# FlightControl.net
KiCad netlist of a schematic drawn in Altium Designer
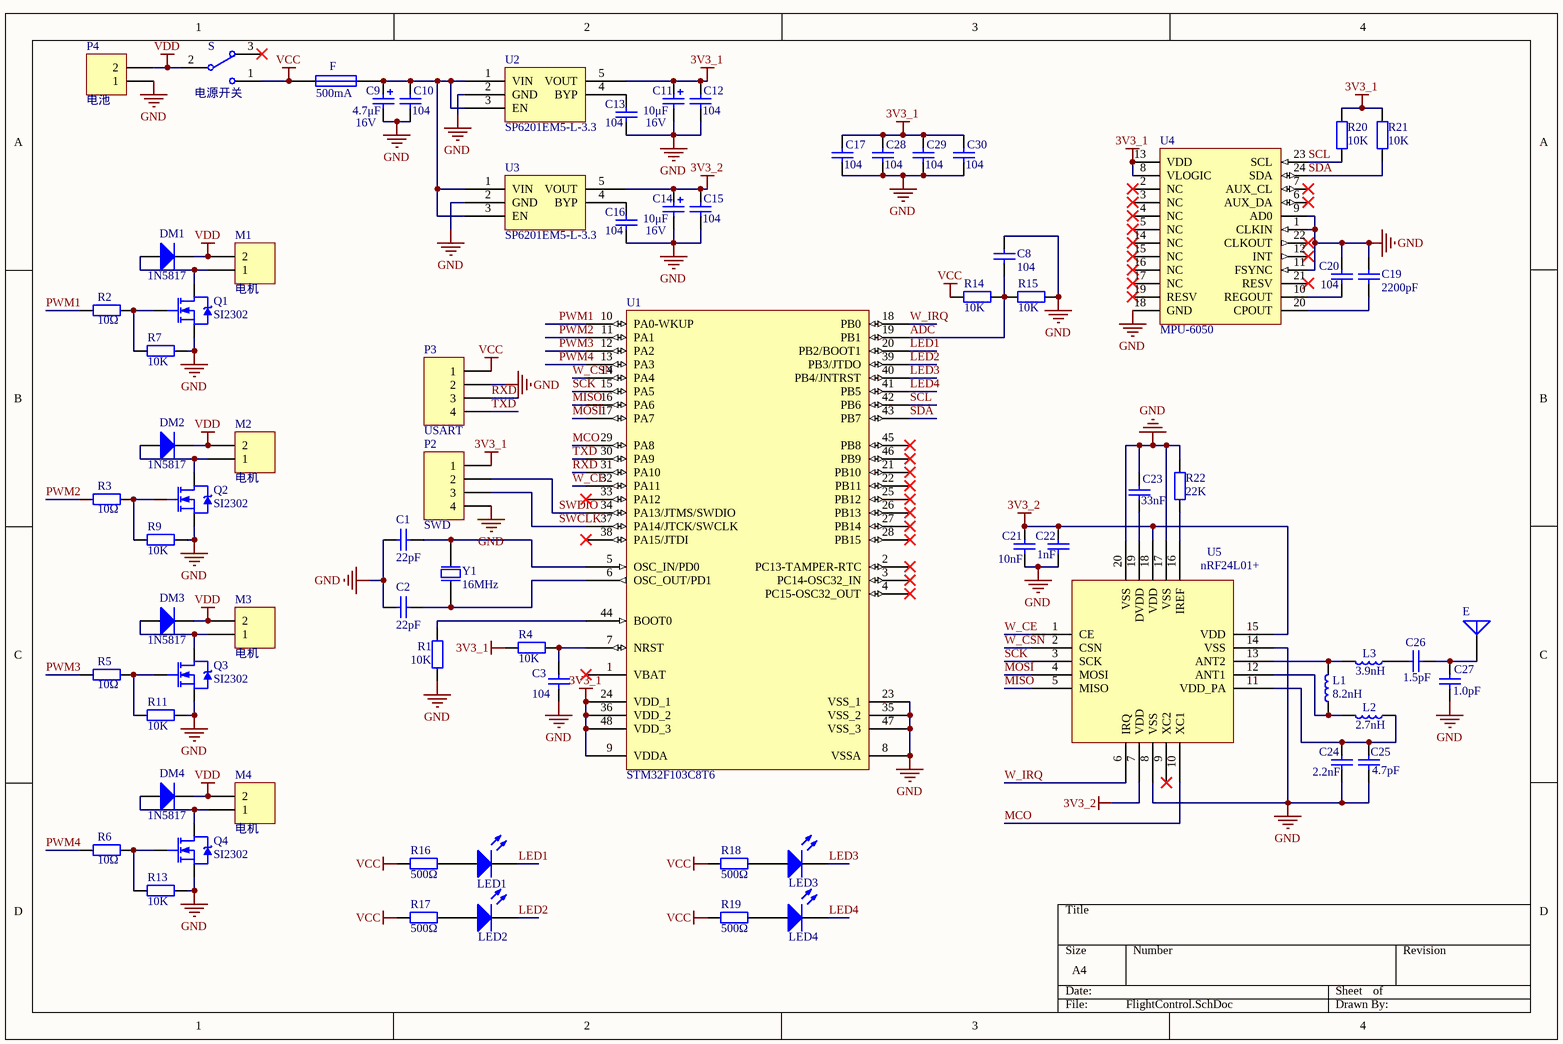
[diagram p0: FlightControl.SchDoc]

(export (version "E")
  (design (tool "Eeschema 10.0.6"))
  (components
    (comp (ref "C1")
      (value "22pF")
      (footprint "CC1608-0603")
      (description "Capacitor")
      (fields (field (name "PUBLISHER") "Altium Limited"))
      (libsource (lib "mini四轴") (part "Cap"))
    )
    (comp (ref "C2")
      (value "22pF")
      (footprint "CC1608-0603")
      (description "Capacitor")
      (fields (field (name "PUBLISHER") "Altium Limited"))
      (libsource (lib "mini四轴") (part "Cap"))
    )
    (comp (ref "C3")
      (value "104")
      (footprint "CC1608-0603")
      (description "Capacitor")
      (fields (field (name "PUBLISHER") "Altium Limited"))
      (libsource (lib "mini四轴") (part "Cap"))
    )
    (comp (ref "C8")
      (value "104")
      (footprint "CC1608-0603")
      (description "Capacitor")
      (fields (field (name "PUBLISHER") "Altium Limited"))
      (libsource (lib "mini四轴") (part "Cap"))
    )
    (comp (ref "C9")
      (value "4.7μF")
      (footprint "TAN-A-3216")
      (description "Polarized Capacitor (Radial)")
      (fields (field (name "VOLTAGE") "16V") (field (name "PUBLISHER") "Altium Limited"))
      (libsource (lib "我的集成库1") (part "Cap Tan"))
    )
    (comp (ref "C10")
      (value "104")
      (footprint "CC1608-0603")
      (description "Capacitor")
      (fields (field (name "PUBLISHER") "Altium Limited"))
      (libsource (lib "mini四轴") (part "Cap"))
    )
    (comp (ref "C11")
      (value "10μF")
      (footprint "TAN-A-3216")
      (description "Polarized Capacitor (Radial)")
      (fields (field (name "VOLTAGE") "16V") (field (name "PUBLISHER") "Altium Limited"))
      (libsource (lib "我的集成库1") (part "Cap Tan"))
    )
    (comp (ref "C12")
      (value "104")
      (footprint "CC1608-0603")
      (description "Capacitor")
      (fields (field (name "PUBLISHER") "Altium Limited"))
      (libsource (lib "mini四轴") (part "Cap"))
    )
    (comp (ref "C13")
      (value "104")
      (footprint "CC1608-0603")
      (description "Capacitor")
      (fields (field (name "PUBLISHER") "Altium Limited"))
      (libsource (lib "mini四轴") (part "Cap"))
    )
    (comp (ref "C14")
      (value "10μF")
      (footprint "TAN-A-3216")
      (description "Polarized Capacitor (Radial)")
      (fields (field (name "VOLTAGE") "16V") (field (name "PUBLISHER") "Altium Limited"))
      (libsource (lib "我的集成库1") (part "Cap Tan"))
    )
    (comp (ref "C15")
      (value "104")
      (footprint "CC1608-0603")
      (description "Capacitor")
      (fields (field (name "PUBLISHER") "Altium Limited"))
      (libsource (lib "mini四轴") (part "Cap"))
    )
    (comp (ref "C16")
      (value "104")
      (footprint "CC1608-0603")
      (description "Capacitor")
      (fields (field (name "PUBLISHER") "Altium Limited"))
      (libsource (lib "mini四轴") (part "Cap"))
    )
    (comp (ref "C17")
      (value "104")
      (footprint "CC1608-0603")
      (description "Capacitor")
      (fields (field (name "PUBLISHER") "Altium Limited"))
      (libsource (lib "mini四轴") (part "Cap"))
    )
    (comp (ref "C19")
      (value "2200pF")
      (footprint "CC1608-0603")
      (description "Capacitor")
      (fields (field (name "PUBLISHER") "Altium Limited"))
      (libsource (lib "mini四轴") (part "Cap"))
    )
    (comp (ref "C20")
      (value "104")
      (footprint "CC1608-0603")
      (description "Capacitor")
      (fields (field (name "PUBLISHER") "Altium Limited"))
      (libsource (lib "mini四轴") (part "Cap"))
    )
    (comp (ref "C21")
      (value "10nF")
      (footprint "CC1608-0603")
      (description "Capacitor")
      (fields (field (name "PUBLISHER") "Altium Limited"))
      (libsource (lib "mini四轴") (part "Cap"))
    )
    (comp (ref "C22")
      (value "1nF")
      (footprint "CC1608-0603")
      (description "Capacitor")
      (fields (field (name "PUBLISHER") "Altium Limited"))
      (libsource (lib "mini四轴") (part "Cap"))
    )
    (comp (ref "C23")
      (value "33nF")
      (footprint "CC1608-0603")
      (description "Capacitor")
      (fields (field (name "PUBLISHER") "Altium Limited"))
      (libsource (lib "mini四轴") (part "Cap"))
    )
    (comp (ref "C24")
      (value "2.2nF")
      (footprint "CC1608-0603")
      (description "Capacitor")
      (fields (field (name "PUBLISHER") "Altium Limited"))
      (libsource (lib "mini四轴") (part "Cap"))
    )
    (comp (ref "C25")
      (value "4.7pF")
      (footprint "CC1608-0603")
      (description "Capacitor")
      (fields (field (name "PUBLISHER") "Altium Limited"))
      (libsource (lib "mini四轴") (part "Cap"))
    )
    (comp (ref "C26")
      (value "1.5pF")
      (footprint "CC1608-0603")
      (description "Capacitor")
      (fields (field (name "PUBLISHER") "Altium Limited"))
      (libsource (lib "mini四轴") (part "Cap"))
    )
    (comp (ref "C27")
      (value "1.0pF")
      (footprint "CC1608-0603")
      (description "Capacitor")
      (fields (field (name "PUBLISHER") "Altium Limited"))
      (libsource (lib "mini四轴") (part "Cap"))
    )
    (comp (ref "C28")
      (value "104")
      (footprint "CC1608-0603")
      (description "Capacitor")
      (fields (field (name "PUBLISHER") "Altium Limited"))
      (libsource (lib "mini四轴") (part "Cap"))
    )
    (comp (ref "C29")
      (value "104")
      (footprint "CC1608-0603")
      (description "Capacitor")
      (fields (field (name "PUBLISHER") "Altium Limited"))
      (libsource (lib "mini四轴") (part "Cap"))
    )
    (comp (ref "C30")
      (value "104")
      (footprint "CC1608-0603")
      (description "Capacitor")
      (fields (field (name "PUBLISHER") "Altium Limited"))
      (libsource (lib "mini四轴") (part "Cap"))
    )
    (comp (ref "DM1")
      (value "1N5817")
      (footprint "SOD-123 (1206)")
      (libsource (lib "我的集成库1") (part "二极管  SOD-323"))
    )
    (comp (ref "DM2")
      (value "1N5817")
      (footprint "SOD-123 (1206)")
      (libsource (lib "我的集成库1") (part "二极管  SOD-323"))
    )
    (comp (ref "DM3")
      (value "1N5817")
      (footprint "SOD-123 (1206)")
      (libsource (lib "我的集成库1") (part "二极管  SOD-323"))
    )
    (comp (ref "DM4")
      (value "1N5817")
      (footprint "SOD-123 (1206)")
      (libsource (lib "我的集成库1") (part "二极管  SOD-323"))
    )
    (comp (ref "E")
      (value "~")
      (footprint "Chip Antenna")
      (description "Generic Antenna")
      (fields (field (name "PUBLISHER") "Altium Limited"))
      (libsource (lib "mini四轴") (part "Antenna"))
    )
    (comp (ref "F")
      (value "500mA")
      (footprint "CR2012-0805")
      (description "Fuse")
      (fields (field (name "PUBLISHER") "Altium Limited"))
      (libsource (lib "我的集成库1") (part "Fuse"))
    )
    (comp (ref "L1")
      (value "8.2nH")
      (footprint "CC1608[0603]")
      (description "Inductor")
      (fields (field (name "PUBLISHER") "Altium Limited"))
      (libsource (lib "mini四轴") (part "Inductor"))
    )
    (comp (ref "L2")
      (value "2.7nH")
      (footprint "CC1608[0603]")
      (description "Inductor")
      (fields (field (name "PUBLISHER") "Altium Limited"))
      (libsource (lib "mini四轴") (part "Inductor"))
    )
    (comp (ref "L3")
      (value "3.9nH")
      (footprint "CC1608[0603]")
      (description "Inductor")
      (fields (field (name "PUBLISHER") "Altium Limited"))
      (libsource (lib "mini四轴") (part "Inductor"))
    )
    (comp (ref "LED1")
      (value "LED Chip")
      (footprint "CLED2012-0805")
      (description "Typical Chip LED")
      (fields (field (name "PUBLISHER") "Altium Limited"))
      (libsource (lib "我的集成库1") (part "LED Chip"))
    )
    (comp (ref "LED2")
      (value "LED Chip")
      (footprint "CLED2012-0805")
      (description "Typical Chip LED")
      (fields (field (name "PUBLISHER") "Altium Limited"))
      (libsource (lib "我的集成库1") (part "LED Chip"))
    )
    (comp (ref "LED3")
      (value "LED Chip")
      (footprint "CLED2012-0805")
      (description "Typical Chip LED")
      (fields (field (name "PUBLISHER") "Altium Limited"))
      (libsource (lib "我的集成库1") (part "LED Chip"))
    )
    (comp (ref "LED4")
      (value "LED Chip")
      (footprint "CLED2012-0805")
      (description "Typical Chip LED")
      (fields (field (name "PUBLISHER") "Altium Limited"))
      (libsource (lib "我的集成库1") (part "LED Chip"))
    )
    (comp (ref "M1")
      (value "电机")
      (footprint "HDR1X2")
      (description "Header, 2-Pin")
      (fields (field (name "PUBLISHER") "Altium Limited"))
      (libsource (lib "我的集成库1") (part "Header 2"))
    )
    (comp (ref "M2")
      (value "电机")
      (footprint "HDR1X2")
      (description "Header, 2-Pin")
      (fields (field (name "PUBLISHER") "Altium Limited"))
      (libsource (lib "我的集成库1") (part "Header 2"))
    )
    (comp (ref "M3")
      (value "电机")
      (footprint "HDR1X2")
      (description "Header, 2-Pin")
      (fields (field (name "PUBLISHER") "Altium Limited"))
      (libsource (lib "我的集成库1") (part "Header 2"))
    )
    (comp (ref "M4")
      (value "电机")
      (footprint "HDR1X2")
      (description "Header, 2-Pin")
      (fields (field (name "PUBLISHER") "Altium Limited"))
      (libsource (lib "我的集成库1") (part "Header 2"))
    )
    (comp (ref "P2")
      (value "SWD")
      (footprint "HDR1X4")
      (description "Header, 4-Pin")
      (fields (field (name "PUBLISHER") "Altium Limited"))
      (libsource (lib "我的集成库1") (part "Header 4"))
    )
    (comp (ref "P3")
      (value "USART")
      (footprint "HDR1X4")
      (description "Header, 4-Pin")
      (fields (field (name "PUBLISHER") "Altium Limited"))
      (libsource (lib "我的集成库1") (part "Header 4"))
    )
    (comp (ref "P4")
      (value "电池")
      (footprint "HDR1X2")
      (description "Header, 2-Pin")
      (fields (field (name "PUBLISHER") "Altium Limited"))
      (libsource (lib "") (part "Header 2_1"))
    )
    (comp (ref "Q1")
      (value "SI2302")
      (footprint "SOT23")
      (description "N-Channel Power MOSFET")
      (fields (field (name "PUBLISHER") "Altium Limited"))
      (libsource (lib "mini四轴") (part "NMOS"))
    )
    (comp (ref "Q2")
      (value "SI2302")
      (footprint "SOT23")
      (description "N-Channel Power MOSFET")
      (fields (field (name "PUBLISHER") "Altium Limited"))
      (libsource (lib "mini四轴") (part "NMOS"))
    )
    (comp (ref "Q3")
      (value "SI2302")
      (footprint "SOT23")
      (description "N-Channel Power MOSFET")
      (fields (field (name "PUBLISHER") "Altium Limited"))
      (libsource (lib "mini四轴") (part "NMOS"))
    )
    (comp (ref "Q4")
      (value "SI2302")
      (footprint "SOT23")
      (description "N-Channel Power MOSFET")
      (fields (field (name "PUBLISHER") "Altium Limited"))
      (libsource (lib "mini四轴") (part "NMOS"))
    )
    (comp (ref "R1")
      (value "10K")
      (footprint "CR1608-0603")
      (description "Resistor")
      (fields (field (name "PUBLISHER") "Altium Limited"))
      (libsource (lib "") (part "Resistor Chip_1"))
    )
    (comp (ref "R2")
      (value "10Ω")
      (footprint "CR1608-0603")
      (description "Resistor")
      (fields (field (name "PUBLISHER") "Altium Limited"))
      (libsource (lib "我的集成库1") (part "Resistor Chip"))
    )
    (comp (ref "R3")
      (value "10Ω")
      (footprint "CR1608-0603")
      (description "Resistor")
      (fields (field (name "PUBLISHER") "Altium Limited"))
      (libsource (lib "我的集成库1") (part "Resistor Chip"))
    )
    (comp (ref "R4")
      (value "10K")
      (footprint "CR1608-0603")
      (description "Resistor")
      (fields (field (name "PUBLISHER") "Altium Limited"))
      (libsource (lib "我的集成库1") (part "Resistor Chip"))
    )
    (comp (ref "R5")
      (value "10Ω")
      (footprint "CR1608-0603")
      (description "Resistor")
      (fields (field (name "PUBLISHER") "Altium Limited"))
      (libsource (lib "我的集成库1") (part "Resistor Chip"))
    )
    (comp (ref "R6")
      (value "10Ω")
      (footprint "CR1608-0603")
      (description "Resistor")
      (fields (field (name "PUBLISHER") "Altium Limited"))
      (libsource (lib "我的集成库1") (part "Resistor Chip"))
    )
    (comp (ref "R7")
      (value "10K")
      (footprint "CR1608-0603")
      (description "Resistor")
      (fields (field (name "PUBLISHER") "Altium Limited"))
      (libsource (lib "我的集成库1") (part "Resistor Chip"))
    )
    (comp (ref "R9")
      (value "10K")
      (footprint "CR1608-0603")
      (description "Resistor")
      (fields (field (name "PUBLISHER") "Altium Limited"))
      (libsource (lib "我的集成库1") (part "Resistor Chip"))
    )
    (comp (ref "R11")
      (value "10K")
      (footprint "CR1608-0603")
      (description "Resistor")
      (fields (field (name "PUBLISHER") "Altium Limited"))
      (libsource (lib "我的集成库1") (part "Resistor Chip"))
    )
    (comp (ref "R13")
      (value "10K")
      (footprint "CR1608-0603")
      (description "Resistor")
      (fields (field (name "PUBLISHER") "Altium Limited"))
      (libsource (lib "我的集成库1") (part "Resistor Chip"))
    )
    (comp (ref "R14")
      (value "10K")
      (footprint "CR1608-0603")
      (description "Resistor")
      (fields (field (name "PUBLISHER") "Altium Limited"))
      (libsource (lib "我的集成库1") (part "Resistor Chip"))
    )
    (comp (ref "R15")
      (value "10K")
      (footprint "CR1608-0603")
      (description "Resistor")
      (fields (field (name "PUBLISHER") "Altium Limited"))
      (libsource (lib "我的集成库1") (part "Resistor Chip"))
    )
    (comp (ref "R16")
      (value "500Ω")
      (footprint "CR1608-0603")
      (description "Resistor")
      (fields (field (name "PUBLISHER") "Altium Limited"))
      (libsource (lib "我的集成库1") (part "Resistor Chip"))
    )
    (comp (ref "R17")
      (value "500Ω")
      (footprint "CR1608-0603")
      (description "Resistor")
      (fields (field (name "PUBLISHER") "Altium Limited"))
      (libsource (lib "我的集成库1") (part "Resistor Chip"))
    )
    (comp (ref "R18")
      (value "500Ω")
      (footprint "CR1608-0603")
      (description "Resistor")
      (fields (field (name "PUBLISHER") "Altium Limited"))
      (libsource (lib "我的集成库1") (part "Resistor Chip"))
    )
    (comp (ref "R19")
      (value "500Ω")
      (footprint "CR1608-0603")
      (description "Resistor")
      (fields (field (name "PUBLISHER") "Altium Limited"))
      (libsource (lib "我的集成库1") (part "Resistor Chip"))
    )
    (comp (ref "R20")
      (value "10K")
      (footprint "CR1608-0603")
      (description "Resistor")
      (fields (field (name "PUBLISHER") "Altium Limited"))
      (libsource (lib "") (part "Resistor Chip_1"))
    )
    (comp (ref "R21")
      (value "10K")
      (footprint "CR1608-0603")
      (description "Resistor")
      (fields (field (name "PUBLISHER") "Altium Limited"))
      (libsource (lib "") (part "Resistor Chip_1"))
    )
    (comp (ref "R22")
      (value "22K")
      (footprint "CR1608-0603")
      (description "Resistor")
      (fields (field (name "PUBLISHER") "Altium Limited"))
      (libsource (lib "") (part "Resistor Chip_1"))
    )
    (comp (ref "S")
      (value "电源开关")
      (footprint "MSK-12C02-1")
      (description "SPDT Subminiature Toggle Switch, Right Angle Mounting, Vertical Actuation")
      (fields (field (name "PUBLISHER") "Altium Limited"))
      (libsource (lib "mini四轴") (part "SW-SPDT"))
    )
    (comp (ref "U1")
      (value "STM32F103C8T6")
      (footprint "LQFP48_N")
      (description "STM32 ARM-based 32-bit MCU with 64 Kbytes Flash, 48-pin LQFP, Industrial Temperature")
      (fields (field (name "PUBLISHER") "*"))
      (libsource (lib "STM32") (part "STM32F103C8T6"))
    )
    (comp (ref "U2")
      (value "SP6201EM5-L-3.3")
      (footprint "SO-G5/NS")
      (libsource (lib "mini四轴") (part "PAM3101"))
    )
    (comp (ref "U3")
      (value "SP6201EM5-L-3.3")
      (footprint "SO-G5/NS")
      (libsource (lib "mini四轴") (part "PAM3101"))
    )
    (comp (ref "U4")
      (value "MPU-6050")
      (footprint "QFN50P400X400X95-24N")
      (description "3-axis gyroscope and 3-axis accelerometer")
      (libsource (lib "mini四轴") (part "MPU-6050"))
    )
    (comp (ref "U5")
      (value "nRF24L01+")
      (footprint "QFN50P400X400-20V5N")
      (libsource (lib "mini四轴") (part "nRF24L01+"))
    )
    (comp (ref "Y1")
      (value "8MHz")
      (footprint "XTAL-PINGBI")
      (description "Crystal Oscillator")
      (fields (field (name "FREQUENCY") "16MHz") (field (name "PUBLISHER") "Altium Limited"))
      (libsource (lib "我的集成库1") (part "XTAL"))
    )
  )
  (nets
    (net (code "1") (name "/ADC") (class "Default")
      (node (ref "C8") (pin "2") (pinfunction "2_2") (pintype "passive"))
      (node (ref "R14") (pin "2") (pinfunction "2_2") (pintype "passive"))
      (node (ref "R15") (pin "1") (pinfunction "1_1") (pintype "passive"))
      (node (ref "U1") (pin "19") (pinfunction "PB1_19") (pintype "bidirectional"))
    )
    (net (code "2") (name "/LED1") (class "Default")
      (node (ref "LED1") (pin "2") (pinfunction "K_2") (pintype "passive"))
      (node (ref "U1") (pin "20") (pinfunction "PB2/BOOT1_20") (pintype "bidirectional"))
    )
    (net (code "3") (name "/LED2") (class "Default")
      (node (ref "LED2") (pin "2") (pinfunction "K_2") (pintype "passive"))
      (node (ref "U1") (pin "39") (pinfunction "PB3/JTDO_39") (pintype "bidirectional"))
    )
    (net (code "4") (name "/LED3") (class "Default")
      (node (ref "LED3") (pin "2") (pinfunction "K_2") (pintype "passive"))
      (node (ref "U1") (pin "40") (pinfunction "PB4/JNTRST_40") (pintype "bidirectional"))
    )
    (net (code "5") (name "/LED4") (class "Default")
      (node (ref "LED4") (pin "2") (pinfunction "K_2") (pintype "passive"))
      (node (ref "U1") (pin "41") (pinfunction "PB5_41") (pintype "bidirectional"))
    )
    (net (code "6") (name "/MCO") (class "Default")
      (node (ref "U1") (pin "29") (pinfunction "PA8_29") (pintype "bidirectional"))
      (node (ref "U5") (pin "10") (pinfunction "XC1_10") (pintype "passive"))
    )
    (net (code "7") (name "/MISO") (class "Default")
      (node (ref "U1") (pin "16") (pinfunction "PA6_16") (pintype "bidirectional"))
      (node (ref "U5") (pin "5") (pinfunction "MISO_5") (pintype "passive"))
    )
    (net (code "8") (name "/MOSI") (class "Default")
      (node (ref "U1") (pin "17") (pinfunction "PA7_17") (pintype "bidirectional"))
      (node (ref "U5") (pin "4") (pinfunction "MOSI_4") (pintype "passive"))
    )
    (net (code "9") (name "/PWM1") (class "Default")
      (node (ref "R2") (pin "1") (pinfunction "1_1") (pintype "passive"))
      (node (ref "U1") (pin "10") (pinfunction "PA0-WKUP_10") (pintype "bidirectional"))
    )
    (net (code "10") (name "/PWM2") (class "Default")
      (node (ref "R3") (pin "1") (pinfunction "1_1") (pintype "passive"))
      (node (ref "U1") (pin "11") (pinfunction "PA1_11") (pintype "bidirectional"))
    )
    (net (code "11") (name "/PWM3") (class "Default")
      (node (ref "R5") (pin "1") (pinfunction "1_1") (pintype "passive"))
      (node (ref "U1") (pin "12") (pinfunction "PA2_12") (pintype "bidirectional"))
    )
    (net (code "12") (name "/PWM4") (class "Default")
      (node (ref "R6") (pin "1") (pinfunction "1_1") (pintype "passive"))
      (node (ref "U1") (pin "13") (pinfunction "PA3_13") (pintype "bidirectional"))
    )
    (net (code "13") (name "/RXD") (class "Default")
      (node (ref "P3") (pin "3") (pinfunction "3_3") (pintype "passive"))
      (node (ref "U1") (pin "31") (pinfunction "PA10_31") (pintype "bidirectional"))
    )
    (net (code "14") (name "/SCK") (class "Default")
      (node (ref "U1") (pin "15") (pinfunction "PA5_15") (pintype "bidirectional"))
      (node (ref "U5") (pin "3") (pinfunction "SCK_3") (pintype "passive"))
    )
    (net (code "15") (name "/SCL") (class "Default")
      (node (ref "R20") (pin "1") (pinfunction "1_1") (pintype "passive"))
      (node (ref "U1") (pin "42") (pinfunction "PB6_42") (pintype "bidirectional"))
      (node (ref "U4") (pin "23") (pinfunction "SCL_23") (pintype "input"))
    )
    (net (code "16") (name "/SDA") (class "Default")
      (node (ref "R21") (pin "1") (pinfunction "1_1") (pintype "passive"))
      (node (ref "U1") (pin "43") (pinfunction "PB7_43") (pintype "bidirectional"))
      (node (ref "U4") (pin "24") (pinfunction "SDA_24") (pintype "bidirectional"))
    )
    (net (code "17") (name "/SWCLK") (class "Default")
      (node (ref "P2") (pin "3") (pinfunction "3_3") (pintype "passive"))
      (node (ref "U1") (pin "37") (pinfunction "PA14/JTCK/SWCLK_37") (pintype "bidirectional"))
    )
    (net (code "18") (name "/SWDIO") (class "Default")
      (node (ref "P2") (pin "2") (pinfunction "2_2") (pintype "passive"))
      (node (ref "U1") (pin "34") (pinfunction "PA13/JTMS/SWDIO_34") (pintype "bidirectional"))
    )
    (net (code "19") (name "/TXD") (class "Default")
      (node (ref "P3") (pin "4") (pinfunction "4_4") (pintype "passive"))
      (node (ref "U1") (pin "30") (pinfunction "PA9_30") (pintype "bidirectional"))
    )
    (net (code "20") (name "/W_CE") (class "Default")
      (node (ref "U1") (pin "32") (pinfunction "PA11_32") (pintype "bidirectional"))
      (node (ref "U5") (pin "1") (pinfunction "CE_1") (pintype "passive"))
    )
    (net (code "21") (name "/W_CSN") (class "Default")
      (node (ref "U1") (pin "14") (pinfunction "PA4_14") (pintype "bidirectional"))
      (node (ref "U5") (pin "2") (pinfunction "CSN_2") (pintype "passive"))
    )
    (net (code "22") (name "/W_IRQ") (class "Default")
      (node (ref "U1") (pin "18") (pinfunction "PB0_18") (pintype "bidirectional"))
      (node (ref "U5") (pin "6") (pinfunction "IRQ_6") (pintype "passive"))
    )
    (net (code "23") (name "3V3_1") (class "Default")
      (node (ref "C11") (pin "2") (pinfunction "1_2") (pintype "passive"))
      (node (ref "C12") (pin "2") (pinfunction "2_2") (pintype "passive"))
      (node (ref "C17") (pin "2") (pinfunction "2_2") (pintype "passive"))
      (node (ref "C28") (pin "2") (pinfunction "2_2") (pintype "passive"))
      (node (ref "C29") (pin "2") (pinfunction "2_2") (pintype "passive"))
      (node (ref "C30") (pin "2") (pinfunction "2_2") (pintype "passive"))
      (node (ref "P2") (pin "1") (pinfunction "1_1") (pintype "passive"))
      (node (ref "R20") (pin "2") (pinfunction "2_2") (pintype "passive"))
      (node (ref "R21") (pin "2") (pinfunction "2_2") (pintype "passive"))
      (node (ref "R4") (pin "1") (pinfunction "1_1") (pintype "passive"))
      (node (ref "U1") (pin "24") (pinfunction "VDD_1_24") (pintype "power_in"))
      (node (ref "U1") (pin "36") (pinfunction "VDD_2_36") (pintype "power_in"))
      (node (ref "U1") (pin "48") (pinfunction "VDD_3_48") (pintype "power_in"))
      (node (ref "U1") (pin "9") (pinfunction "VDDA_9") (pintype "power_in"))
      (node (ref "U2") (pin "5") (pinfunction "VOUT_5") (pintype "passive"))
      (node (ref "U4") (pin "13") (pinfunction "VDD_13") (pintype "power_in"))
      (node (ref "U4") (pin "8") (pinfunction "VLOGIC_8") (pintype "power_in"))
    )
    (net (code "24") (name "3V3_2") (class "Default")
      (node (ref "C14") (pin "2") (pinfunction "1_2") (pintype "passive"))
      (node (ref "C15") (pin "2") (pinfunction "2_2") (pintype "passive"))
      (node (ref "C21") (pin "1") (pinfunction "1_1") (pintype "passive"))
      (node (ref "C22") (pin "1") (pinfunction "1_1") (pintype "passive"))
      (node (ref "U3") (pin "5") (pinfunction "VOUT_5") (pintype "passive"))
      (node (ref "U5") (pin "15") (pinfunction "VDD_15") (pintype "passive"))
      (node (ref "U5") (pin "18") (pinfunction "VDD_18") (pintype "passive"))
      (node (ref "U5") (pin "7") (pinfunction "VDD_7") (pintype "passive"))
    )
    (net (code "25") (name "GND") (class "Default")
      (node (ref "C1") (pin "1") (pinfunction "1_1") (pintype "passive"))
      (node (ref "C10") (pin "1") (pinfunction "1_1") (pintype "passive"))
      (node (ref "C11") (pin "1") (pinfunction "2_1") (pintype "passive"))
      (node (ref "C12") (pin "1") (pinfunction "1_1") (pintype "passive"))
      (node (ref "C13") (pin "1") (pinfunction "1_1") (pintype "passive"))
      (node (ref "C14") (pin "1") (pinfunction "2_1") (pintype "passive"))
      (node (ref "C15") (pin "1") (pinfunction "1_1") (pintype "passive"))
      (node (ref "C16") (pin "1") (pinfunction "1_1") (pintype "passive"))
      (node (ref "C17") (pin "1") (pinfunction "1_1") (pintype "passive"))
      (node (ref "C19") (pin "1") (pinfunction "1_1") (pintype "passive"))
      (node (ref "C2") (pin "1") (pinfunction "1_1") (pintype "passive"))
      (node (ref "C20") (pin "1") (pinfunction "1_1") (pintype "passive"))
      (node (ref "C21") (pin "2") (pinfunction "2_2") (pintype "passive"))
      (node (ref "C22") (pin "2") (pinfunction "2_2") (pintype "passive"))
      (node (ref "C23") (pin "1") (pinfunction "1_1") (pintype "passive"))
      (node (ref "C24") (pin "2") (pinfunction "2_2") (pintype "passive"))
      (node (ref "C25") (pin "2") (pinfunction "2_2") (pintype "passive"))
      (node (ref "C27") (pin "1") (pinfunction "1_1") (pintype "passive"))
      (node (ref "C28") (pin "1") (pinfunction "1_1") (pintype "passive"))
      (node (ref "C29") (pin "1") (pinfunction "1_1") (pintype "passive"))
      (node (ref "C3") (pin "1") (pinfunction "1_1") (pintype "passive"))
      (node (ref "C30") (pin "1") (pinfunction "1_1") (pintype "passive"))
      (node (ref "C8") (pin "1") (pinfunction "1_1") (pintype "passive"))
      (node (ref "C9") (pin "1") (pinfunction "2_1") (pintype "passive"))
      (node (ref "P2") (pin "4") (pinfunction "4_4") (pintype "passive"))
      (node (ref "P3") (pin "2") (pinfunction "2_2") (pintype "passive"))
      (node (ref "P4") (pin "1") (pinfunction "1_1") (pintype "passive"))
      (node (ref "Q1") (pin "3") (pinfunction "S_3") (pintype "passive"))
      (node (ref "Q2") (pin "3") (pinfunction "S_3") (pintype "passive"))
      (node (ref "Q3") (pin "3") (pinfunction "S_3") (pintype "passive"))
      (node (ref "Q4") (pin "3") (pinfunction "S_3") (pintype "passive"))
      (node (ref "R1") (pin "1") (pinfunction "1_1") (pintype "passive"))
      (node (ref "R11") (pin "2") (pinfunction "2_2") (pintype "passive"))
      (node (ref "R13") (pin "2") (pinfunction "2_2") (pintype "passive"))
      (node (ref "R15") (pin "2") (pinfunction "2_2") (pintype "passive"))
      (node (ref "R22") (pin "2") (pinfunction "2_2") (pintype "passive"))
      (node (ref "R7") (pin "2") (pinfunction "2_2") (pintype "passive"))
      (node (ref "R9") (pin "2") (pinfunction "2_2") (pintype "passive"))
      (node (ref "U1") (pin "23") (pinfunction "VSS_1_23") (pintype "power_in"))
      (node (ref "U1") (pin "35") (pinfunction "VSS_2_35") (pintype "power_in"))
      (node (ref "U1") (pin "47") (pinfunction "VSS_3_47") (pintype "power_in"))
      (node (ref "U1") (pin "8") (pinfunction "VSSA_8") (pintype "power_in"))
      (node (ref "U2") (pin "2") (pinfunction "GND_2") (pintype "passive"))
      (node (ref "U3") (pin "2") (pinfunction "GND_2") (pintype "passive"))
      (node (ref "U4") (pin "1") (pinfunction "CLKIN_1") (pintype "input"))
      (node (ref "U4") (pin "11") (pinfunction "FSYNC_11") (pintype "input"))
      (node (ref "U4") (pin "18") (pinfunction "GND_18") (pintype "power_in"))
      (node (ref "U4") (pin "9") (pinfunction "AD0_9") (pintype "power_in"))
      (node (ref "U5") (pin "14") (pinfunction "VSS_14") (pintype "passive"))
      (node (ref "U5") (pin "17") (pinfunction "VSS_17") (pintype "passive"))
      (node (ref "U5") (pin "20") (pinfunction "VSS_20") (pintype "passive"))
      (node (ref "U5") (pin "8") (pinfunction "VSS_8") (pintype "passive"))
    )
    (net (code "26") (name "Net-(C9-1)") (class "Default")
      (node (ref "C10") (pin "2") (pinfunction "2_2") (pintype "passive"))
      (node (ref "C9") (pin "2") (pinfunction "1_2") (pintype "passive"))
      (node (ref "F") (pin "2") (pinfunction "2_2") (pintype "passive"))
      (node (ref "U2") (pin "1") (pinfunction "VIN_1") (pintype "passive"))
      (node (ref "U2") (pin "3") (pinfunction "EN_3") (pintype "passive"))
      (node (ref "U3") (pin "1") (pinfunction "VIN_1") (pintype "passive"))
      (node (ref "U3") (pin "3") (pinfunction "EN_3") (pintype "passive"))
    )
    (net (code "27") (name "Net-(C26-Pad1)") (class "Default")
      (node (ref "C26") (pin "1") (pinfunction "1_1") (pintype "passive"))
      (node (ref "L3") (pin "1") (pinfunction "1_1") (pintype "passive"))
    )
    (net (code "28") (name "Net-(DM1-A)") (class "Default")
      (node (ref "DM1") (pin "1") (pinfunction "A_1") (pintype "passive"))
      (node (ref "M1") (pin "1") (pinfunction "1_1") (pintype "passive"))
      (node (ref "Q1") (pin "2") (pinfunction "D_2") (pintype "passive"))
    )
    (net (code "29") (name "Net-(DM2-A)") (class "Default")
      (node (ref "DM2") (pin "1") (pinfunction "A_1") (pintype "passive"))
      (node (ref "M2") (pin "1") (pinfunction "1_1") (pintype "passive"))
      (node (ref "Q2") (pin "2") (pinfunction "D_2") (pintype "passive"))
    )
    (net (code "30") (name "Net-(DM3-A)") (class "Default")
      (node (ref "DM3") (pin "1") (pinfunction "A_1") (pintype "passive"))
      (node (ref "M3") (pin "1") (pinfunction "1_1") (pintype "passive"))
      (node (ref "Q3") (pin "2") (pinfunction "D_2") (pintype "passive"))
    )
    (net (code "31") (name "Net-(DM4-A)") (class "Default")
      (node (ref "DM4") (pin "1") (pinfunction "A_1") (pintype "passive"))
      (node (ref "M4") (pin "1") (pinfunction "1_1") (pintype "passive"))
      (node (ref "Q4") (pin "2") (pinfunction "D_2") (pintype "passive"))
    )
    (net (code "32") (name "Net-(E-A)") (class "Default")
      (node (ref "C26") (pin "2") (pinfunction "2_2") (pintype "passive"))
      (node (ref "C27") (pin "2") (pinfunction "2_2") (pintype "passive"))
      (node (ref "E") (pin "1") (pinfunction "A_1") (pintype "passive"))
    )
    (net (code "33") (name "Net-(LED1-A)") (class "Default")
      (node (ref "LED1") (pin "1") (pinfunction "A_1") (pintype "passive"))
      (node (ref "R16") (pin "2") (pinfunction "2_2") (pintype "passive"))
    )
    (net (code "34") (name "Net-(LED2-A)") (class "Default")
      (node (ref "LED2") (pin "1") (pinfunction "A_1") (pintype "passive"))
      (node (ref "R17") (pin "2") (pinfunction "2_2") (pintype "passive"))
    )
    (net (code "35") (name "Net-(LED3-A)") (class "Default")
      (node (ref "LED3") (pin "1") (pinfunction "A_1") (pintype "passive"))
      (node (ref "R18") (pin "2") (pinfunction "2_2") (pintype "passive"))
    )
    (net (code "36") (name "Net-(LED4-A)") (class "Default")
      (node (ref "LED4") (pin "1") (pinfunction "A_1") (pintype "passive"))
      (node (ref "R19") (pin "2") (pinfunction "2_2") (pintype "passive"))
    )
    (net (code "37") (name "Net-(Q1-G)") (class "Default")
      (node (ref "Q1") (pin "1") (pinfunction "G_1") (pintype "passive"))
      (node (ref "R2") (pin "2") (pinfunction "2_2") (pintype "passive"))
      (node (ref "R7") (pin "1") (pinfunction "1_1") (pintype "passive"))
    )
    (net (code "38") (name "Net-(Q2-G)") (class "Default")
      (node (ref "Q2") (pin "1") (pinfunction "G_1") (pintype "passive"))
      (node (ref "R3") (pin "2") (pinfunction "2_2") (pintype "passive"))
      (node (ref "R9") (pin "1") (pinfunction "1_1") (pintype "passive"))
    )
    (net (code "39") (name "Net-(Q3-G)") (class "Default")
      (node (ref "Q3") (pin "1") (pinfunction "G_1") (pintype "passive"))
      (node (ref "R11") (pin "1") (pinfunction "1_1") (pintype "passive"))
      (node (ref "R5") (pin "2") (pinfunction "2_2") (pintype "passive"))
    )
    (net (code "40") (name "Net-(Q4-G)") (class "Default")
      (node (ref "Q4") (pin "1") (pinfunction "G_1") (pintype "passive"))
      (node (ref "R13") (pin "1") (pinfunction "1_1") (pintype "passive"))
      (node (ref "R6") (pin "2") (pinfunction "2_2") (pintype "passive"))
    )
    (net (code "41") (name "Net-(U1-BOOT0)") (class "Default")
      (node (ref "R1") (pin "2") (pinfunction "2_2") (pintype "passive"))
      (node (ref "U1") (pin "44") (pinfunction "BOOT0_44") (pintype "input"))
    )
    (net (code "42") (name "Net-(U1-NRST)") (class "Default")
      (node (ref "C3") (pin "2") (pinfunction "2_2") (pintype "passive"))
      (node (ref "R4") (pin "2") (pinfunction "2_2") (pintype "passive"))
      (node (ref "U1") (pin "7") (pinfunction "NRST_7") (pintype "bidirectional"))
    )
    (net (code "43") (name "Net-(U1-OSC_IN{slash}PD0)") (class "Default")
      (node (ref "C1") (pin "2") (pinfunction "2_2") (pintype "passive"))
      (node (ref "U1") (pin "5") (pinfunction "OSC_IN/PD0_5") (pintype "input"))
      (node (ref "Y1") (pin "2") (pinfunction "OSC2_2") (pintype "passive"))
    )
    (net (code "44") (name "Net-(U1-OSC_OUT{slash}PD1)") (class "Default")
      (node (ref "C2") (pin "2") (pinfunction "2_2") (pintype "passive"))
      (node (ref "U1") (pin "6") (pinfunction "OSC_OUT/PD1_6") (pintype "output"))
      (node (ref "Y1") (pin "1") (pinfunction "OSC1_1") (pintype "passive"))
    )
    (net (code "45") (name "Net-(U2-BYP)") (class "Default")
      (node (ref "C13") (pin "2") (pinfunction "2_2") (pintype "passive"))
      (node (ref "U2") (pin "4") (pinfunction "BYP_4") (pintype "passive"))
    )
    (net (code "46") (name "Net-(U3-BYP)") (class "Default")
      (node (ref "C16") (pin "2") (pinfunction "2_2") (pintype "passive"))
      (node (ref "U3") (pin "4") (pinfunction "BYP_4") (pintype "passive"))
    )
    (net (code "47") (name "Net-(U4-CPOUT)") (class "Default")
      (node (ref "C19") (pin "2") (pinfunction "2_2") (pintype "passive"))
      (node (ref "U4") (pin "20") (pinfunction "CPOUT_20") (pintype "passive"))
    )
    (net (code "48") (name "Net-(U4-REGOUT)") (class "Default")
      (node (ref "C20") (pin "2") (pinfunction "2_2") (pintype "passive"))
      (node (ref "U4") (pin "10") (pinfunction "REGOUT_10") (pintype "power_in"))
    )
    (net (code "49") (name "Net-(U5-ANT1)") (class "Default")
      (node (ref "L1") (pin "1") (pinfunction "1_1") (pintype "passive"))
      (node (ref "L2") (pin "2") (pinfunction "2_2") (pintype "passive"))
      (node (ref "U5") (pin "12") (pinfunction "ANT1_12") (pintype "passive"))
    )
    (net (code "50") (name "Net-(U5-ANT2)") (class "Default")
      (node (ref "L1") (pin "2") (pinfunction "2_2") (pintype "passive"))
      (node (ref "L3") (pin "2") (pinfunction "2_2") (pintype "passive"))
      (node (ref "U5") (pin "13") (pinfunction "ANT2_13") (pintype "passive"))
    )
    (net (code "51") (name "Net-(U5-DVDD)") (class "Default")
      (node (ref "C23") (pin "2") (pinfunction "2_2") (pintype "passive"))
      (node (ref "U5") (pin "19") (pinfunction "DVDD_19") (pintype "passive"))
    )
    (net (code "52") (name "Net-(U5-IREF)") (class "Default")
      (node (ref "R22") (pin "1") (pinfunction "1_1") (pintype "passive"))
      (node (ref "U5") (pin "16") (pinfunction "IREF_16") (pintype "passive"))
    )
    (net (code "53") (name "Net-(U5-VDD_PA)") (class "Default")
      (node (ref "C24") (pin "1") (pinfunction "1_1") (pintype "passive"))
      (node (ref "C25") (pin "1") (pinfunction "1_1") (pintype "passive"))
      (node (ref "L2") (pin "1") (pinfunction "1_1") (pintype "passive"))
      (node (ref "U5") (pin "11") (pinfunction "VDD_PA_11") (pintype "passive"))
    )
    (net (code "54") (name "VCC") (class "Default")
      (node (ref "F") (pin "1") (pinfunction "1_1") (pintype "passive"))
      (node (ref "P3") (pin "1") (pinfunction "1_1") (pintype "passive"))
      (node (ref "R14") (pin "1") (pinfunction "1_1") (pintype "passive"))
      (node (ref "R16") (pin "1") (pinfunction "1_1") (pintype "passive"))
      (node (ref "R17") (pin "1") (pinfunction "1_1") (pintype "passive"))
      (node (ref "R18") (pin "1") (pinfunction "1_1") (pintype "passive"))
      (node (ref "R19") (pin "1") (pinfunction "1_1") (pintype "passive"))
      (node (ref "S") (pin "1") (pinfunction "1_1") (pintype "passive"))
    )
    (net (code "55") (name "VDD") (class "Default")
      (node (ref "DM1") (pin "2") (pinfunction "K_2") (pintype "passive"))
      (node (ref "DM2") (pin "2") (pinfunction "K_2") (pintype "passive"))
      (node (ref "DM3") (pin "2") (pinfunction "K_2") (pintype "passive"))
      (node (ref "DM4") (pin "2") (pinfunction "K_2") (pintype "passive"))
      (node (ref "M1") (pin "2") (pinfunction "2_2") (pintype "passive"))
      (node (ref "M2") (pin "2") (pinfunction "2_2") (pintype "passive"))
      (node (ref "M3") (pin "2") (pinfunction "2_2") (pintype "passive"))
      (node (ref "M4") (pin "2") (pinfunction "2_2") (pintype "passive"))
      (node (ref "P4") (pin "2") (pinfunction "2_2") (pintype "passive"))
      (node (ref "S") (pin "2") (pinfunction "2_2") (pintype "passive"))
    )
    (net (code "56") (name "unconnected-(S-Pad3)") (class "Default")
      (node (ref "S") (pin "3") (pinfunction "3_3") (pintype "passive+no_connect"))
    )
    (net (code "57") (name "unconnected-(U1-PA12-Pad33)") (class "Default")
      (node (ref "U1") (pin "33") (pinfunction "PA12_33") (pintype "bidirectional+no_connect"))
    )
    (net (code "58") (name "unconnected-(U1-PA15{slash}JTDI-Pad38)") (class "Default")
      (node (ref "U1") (pin "38") (pinfunction "PA15/JTDI_38") (pintype "bidirectional+no_connect"))
    )
    (net (code "59") (name "unconnected-(U1-PB8-Pad45)") (class "Default")
      (node (ref "U1") (pin "45") (pinfunction "PB8_45") (pintype "bidirectional+no_connect"))
    )
    (net (code "60") (name "unconnected-(U1-PB9-Pad46)") (class "Default")
      (node (ref "U1") (pin "46") (pinfunction "PB9_46") (pintype "bidirectional+no_connect"))
    )
    (net (code "61") (name "unconnected-(U1-PB10-Pad21)") (class "Default")
      (node (ref "U1") (pin "21") (pinfunction "PB10_21") (pintype "bidirectional+no_connect"))
    )
    (net (code "62") (name "unconnected-(U1-PB11-Pad22)") (class "Default")
      (node (ref "U1") (pin "22") (pinfunction "PB11_22") (pintype "bidirectional+no_connect"))
    )
    (net (code "63") (name "unconnected-(U1-PB12-Pad25)") (class "Default")
      (node (ref "U1") (pin "25") (pinfunction "PB12_25") (pintype "bidirectional+no_connect"))
    )
    (net (code "64") (name "unconnected-(U1-PB13-Pad26)") (class "Default")
      (node (ref "U1") (pin "26") (pinfunction "PB13_26") (pintype "bidirectional+no_connect"))
    )
    (net (code "65") (name "unconnected-(U1-PB14-Pad27)") (class "Default")
      (node (ref "U1") (pin "27") (pinfunction "PB14_27") (pintype "bidirectional+no_connect"))
    )
    (net (code "66") (name "unconnected-(U1-PB15-Pad28)") (class "Default")
      (node (ref "U1") (pin "28") (pinfunction "PB15_28") (pintype "bidirectional+no_connect"))
    )
    (net (code "67") (name "unconnected-(U1-PC13-TAMPER-RTC-Pad2)") (class "Default")
      (node (ref "U1") (pin "2") (pinfunction "PC13-TAMPER-RTC_2") (pintype "bidirectional+no_connect"))
    )
    (net (code "68") (name "unconnected-(U1-PC14-OSC32_IN-Pad3)") (class "Default")
      (node (ref "U1") (pin "3") (pinfunction "PC14-OSC32_IN_3") (pintype "bidirectional+no_connect"))
    )
    (net (code "69") (name "unconnected-(U1-PC15-OSC32_OUT-Pad4)") (class "Default")
      (node (ref "U1") (pin "4") (pinfunction "PC15-OSC32_OUT_4") (pintype "bidirectional+no_connect"))
    )
    (net (code "70") (name "unconnected-(U1-VBAT-Pad1)") (class "Default")
      (node (ref "U1") (pin "1") (pinfunction "VBAT_1") (pintype "power_in+no_connect"))
    )
    (net (code "71") (name "unconnected-(U4-AUX_CL-Pad7)") (class "Default")
      (node (ref "U4") (pin "7") (pinfunction "AUX_CL_7") (pintype "bidirectional+no_connect"))
    )
    (net (code "72") (name "unconnected-(U4-AUX_DA-Pad6)") (class "Default")
      (node (ref "U4") (pin "6") (pinfunction "AUX_DA_6") (pintype "bidirectional+no_connect"))
    )
    (net (code "73") (name "unconnected-(U4-CLKOUT-Pad22)") (class "Default")
      (node (ref "U4") (pin "22") (pinfunction "CLKOUT_22") (pintype "output+no_connect"))
    )
    (net (code "74") (name "unconnected-(U4-INT-Pad12)") (class "Default")
      (node (ref "U4") (pin "12") (pinfunction "INT_12") (pintype "output+no_connect"))
    )
    (net (code "75") (name "unconnected-(U4-NC-Pad2)") (class "Default")
      (node (ref "U4") (pin "2") (pinfunction "NC_2") (pintype "passive+no_connect"))
    )
    (net (code "76") (name "unconnected-(U4-NC-Pad3)") (class "Default")
      (node (ref "U4") (pin "3") (pinfunction "NC_3") (pintype "passive+no_connect"))
    )
    (net (code "77") (name "unconnected-(U4-NC-Pad4)") (class "Default")
      (node (ref "U4") (pin "4") (pinfunction "NC_4") (pintype "passive+no_connect"))
    )
    (net (code "78") (name "unconnected-(U4-NC-Pad5)") (class "Default")
      (node (ref "U4") (pin "5") (pinfunction "NC_5") (pintype "passive+no_connect"))
    )
    (net (code "79") (name "unconnected-(U4-NC-Pad14)") (class "Default")
      (node (ref "U4") (pin "14") (pinfunction "NC_14") (pintype "passive+no_connect"))
    )
    (net (code "80") (name "unconnected-(U4-NC-Pad15)") (class "Default")
      (node (ref "U4") (pin "15") (pinfunction "NC_15") (pintype "passive+no_connect"))
    )
    (net (code "81") (name "unconnected-(U4-NC-Pad16)") (class "Default")
      (node (ref "U4") (pin "16") (pinfunction "NC_16") (pintype "passive+no_connect"))
    )
    (net (code "82") (name "unconnected-(U4-NC-Pad17)") (class "Default")
      (node (ref "U4") (pin "17") (pinfunction "NC_17") (pintype "passive+no_connect"))
    )
    (net (code "83") (name "unconnected-(U4-RESV-Pad19)") (class "Default")
      (node (ref "U4") (pin "19") (pinfunction "RESV_19") (pintype "passive+no_connect"))
    )
    (net (code "84") (name "unconnected-(U4-RESV-Pad21)") (class "Default")
      (node (ref "U4") (pin "21") (pinfunction "RESV_21") (pintype "passive+no_connect"))
    )
    (net (code "85") (name "unconnected-(U5-XC2-Pad9)") (class "Default")
      (node (ref "U5") (pin "9") (pinfunction "XC2_9") (pintype "passive+no_connect"))
    )
  )
)
